# board_schematic.net
KiCad netlist of a schematic drawn in Altium Designer
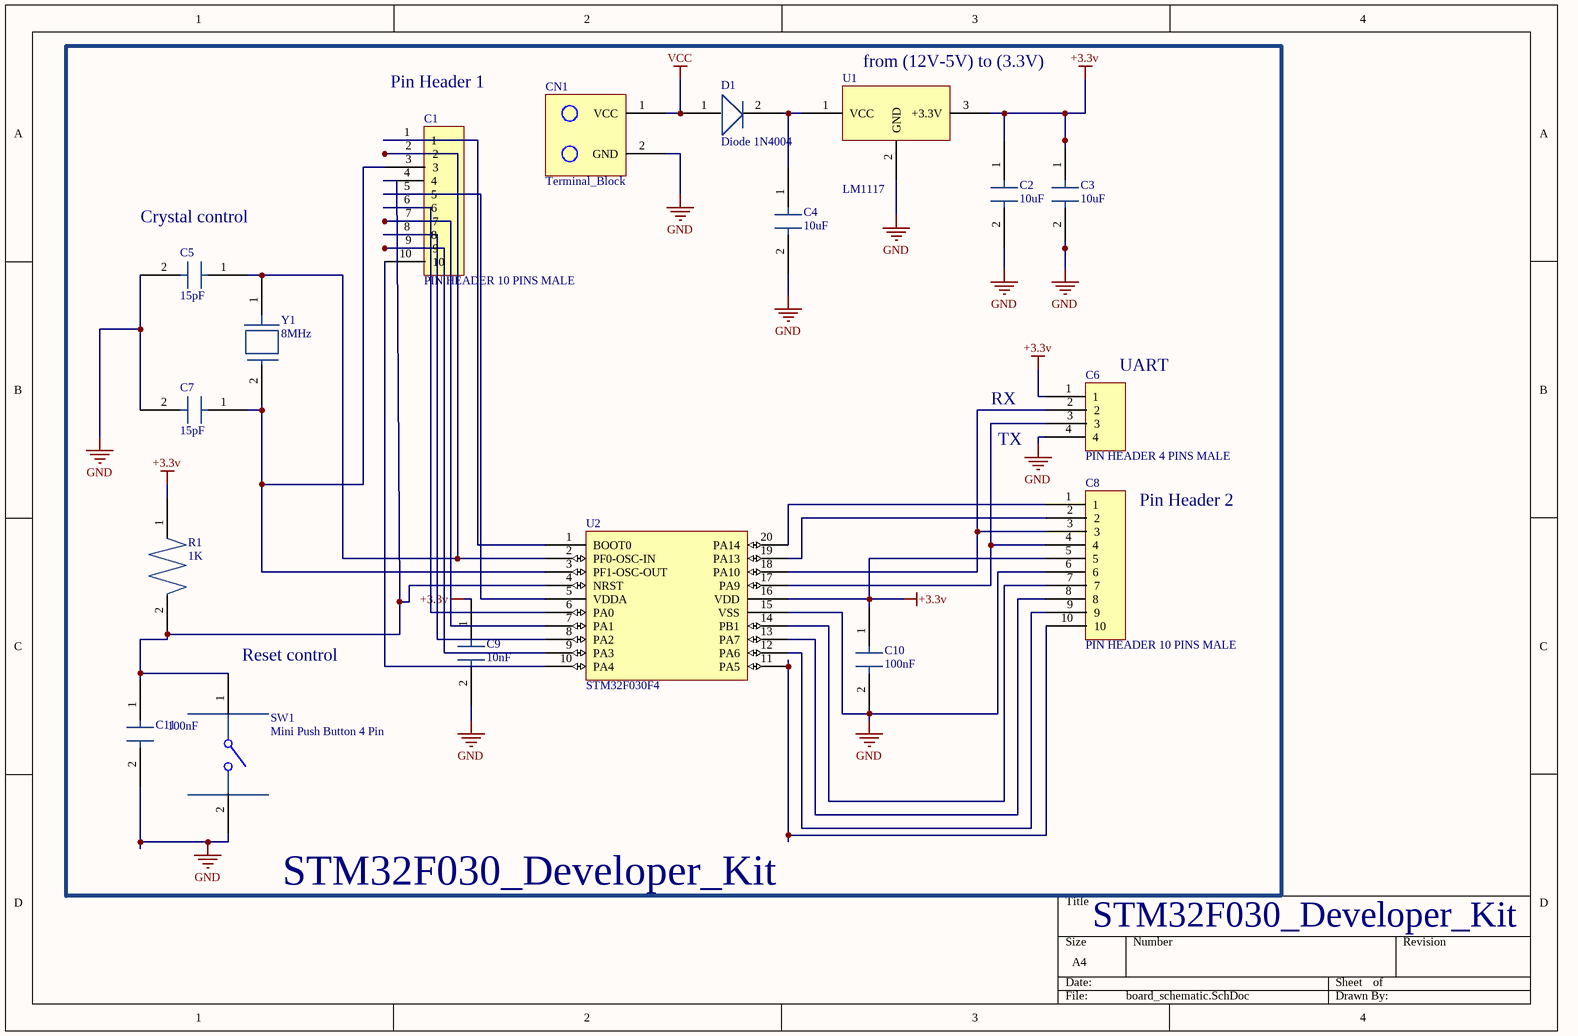
[diagram p0: board_schematic.SchDoc]

(export (version "E")
  (design (tool "Eeschema 10.0.6"))
  (components
    (comp (ref "C1")
      (value "PIN HEADER 10 PINS MALE")
      (footprint "PIN HEADER 10 PINS MALE")
      (description "Through Hole 1way 10pins")
      (fields (field (name "MANUFACTURER") "ZHOURI") (field (name "MANUFACTURER PART NUMBER") "2.54-1*10"))
      (libsource (lib "stm_library") (part "PIN HEADER 10 PINS MALE"))
    )
    (comp (ref "C2")
      (value "10uF")
      (footprint "CAP 220nF SMD")
      (description "25V 10uF Y5V ±10% 1206 Multilayer Ceramic Capacitors MLCC – SMD/SMT ROHS")
      (fields
        (field (name "MANUFACTURER") "CCTC")
        (field (name "MANUFACTURER PART NUMBER") "TCC1206X5R106K250HT")
      )
      (libsource (lib "stm_library") (part "CAP 10uF SMD"))
    )
    (comp (ref "C3")
      (value "10uF")
      (footprint "CAP 220nF SMD")
      (description "25V 10uF Y5V ±10% 1206 Multilayer Ceramic Capacitors MLCC – SMD/SMT ROHS")
      (fields
        (field (name "MANUFACTURER") "CCTC")
        (field (name "MANUFACTURER PART NUMBER") "TCC1206X5R106K250HT")
      )
      (libsource (lib "stm_library") (part "CAP 10uF SMD"))
    )
    (comp (ref "C4")
      (value "10uF")
      (footprint "CAP 220nF SMD")
      (description "25V 10uF Y5V ±10% 1206 Multilayer Ceramic Capacitors MLCC – SMD/SMT ROHS")
      (fields
        (field (name "MANUFACTURER") "CCTC")
        (field (name "MANUFACTURER PART NUMBER") "TCC1206X5R106K250HT")
      )
      (libsource (lib "stm_library") (part "CAP 10uF SMD"))
    )
    (comp (ref "C5")
      (value "15pF")
      (footprint "CAP 15pF SMD")
      (description "50V 15pF C0G ±5% 0603 Multilayer Ceramic Capacitors MLCC – SMD/SMT ROHS– SMD/SMT ROHS")
      (fields
        (field (name "MANUFACTURER") "CCTC")
        (field (name "MANUFACTURER PART NUMBER") "TCC0603COG150J500CT")
      )
      (libsource (lib "stm_library") (part "CAP 15pF SMD"))
    )
    (comp (ref "C6")
      (value "PIN HEADER 4 PINS MALE")
      (footprint "PIN HEADER 4 PINS MALE")
      (description "Through Hole 1way 4pins")
      (fields (field (name "MANUFACTURER") "ZHOURI") (field (name "MANUFACTURER PART NUMBER") "2.54-1*4"))
      (libsource (lib "stm_library") (part "PIN HEADER 4 PINS MALE"))
    )
    (comp (ref "C7")
      (value "15pF")
      (footprint "CAP 15pF SMD")
      (description "50V 15pF C0G ±5% 0603 Multilayer Ceramic Capacitors MLCC – SMD/SMT ROHS– SMD/SMT ROHS")
      (fields
        (field (name "MANUFACTURER") "CCTC")
        (field (name "MANUFACTURER PART NUMBER") "TCC0603COG150J500CT")
      )
      (libsource (lib "stm_library") (part "CAP 15pF SMD"))
    )
    (comp (ref "C8")
      (value "PIN HEADER 10 PINS MALE")
      (footprint "PIN HEADER 10 PINS MALE")
      (description "Through Hole 1way 10pins")
      (fields (field (name "MANUFACTURER") "ZHOURI") (field (name "MANUFACTURER PART NUMBER") "2.54-1*10"))
      (libsource (lib "stm_library") (part "PIN HEADER 10 PINS MALE"))
    )
    (comp (ref "C9")
      (value "10nF")
      (footprint "CAP 220nF SMD")
      (description "50V 10nF X7R ±10% 1206 Multilayer Ceramic Capacitors MLCC – SMD/SMT ROHS")
      (fields
        (field (name "MANUFACTURER") "CCTC")
        (field (name "MANUFACTURER PART NUMBER") "TCC1206X7R103K500DT")
      )
      (libsource (lib "stm_library") (part "CAP 10nF SMD"))
    )
    (comp (ref "C10")
      (value "100nF")
      (footprint "CAP 100nF SMD")
      (description "16V 100nF X7R ±10% 0402 Multilayer Ceramic Capacitors MLCC – SMD/SMT ROHS")
      (fields
        (field (name "MANUFACTURER") "Samsung Electro-Mechanics")
        (field (name "MANUFACTURER PART NUMBER") "CL05B104KO5NNNC")
      )
      (libsource (lib "stm_library") (part "CAP 100nF SMD"))
    )
    (comp (ref "C11")
      (value "100nF")
      (footprint "CAP 100nF SMD")
      (description "16V 100nF X7R ±10% 0402 Multilayer Ceramic Capacitors MLCC – SMD/SMT ROHS")
      (fields
        (field (name "MANUFACTURER") "Samsung Electro-Mechanics")
        (field (name "MANUFACTURER PART NUMBER") "CL05B104KO5NNNC")
      )
      (libsource (lib "stm_library") (part "CAP 100nF SMD"))
    )
    (comp (ref "CN1")
      (value "Terminal_Block")
      (footprint "TerminalBlock_2pins")
      (fields
        (field (name "MANUFACTURER") "CUI Devices")
        (field (name "MANUFACTURER PART NUMBER") "TB002-500-02BE")
      )
      (libsource (lib "stm_library") (part "Terminal_Block"))
    )
    (comp (ref "D1")
      (value "Diode 1N4004")
      (footprint "Diode 1N4004")
      (description "Single 1A 1.1V@1A 400V SMA Diodes – General Purpose ROHS")
      (fields (field (name "MANUFACTURER") "YONGYUTAI") (field (name "MANUFACTURER PART NUMBER") "1N4004"))
      (libsource (lib "stm_library") (part "Diode 1N4004"))
    )
    (comp (ref "R1")
      (value "1K")
      (footprint "RES 10K SMD")
      (description "Chip Resistor SMD 1KΩ ±5% 1W ±100ppm/℃ 2512")
      (fields
        (field (name "MANUFACTURER") "FOJAN")
        (field (name "MANUFACTURER PART NUMBER") "FRC2512J103 TS")
      )
      (libsource (lib "stm_library") (part "RES 1K SMD"))
    )
    (comp (ref "SW1")
      (value "Mini Push Button 4 Pin")
      (footprint "Mini Push Button 4 Pin")
      (description "6x6x7mm Tactile 4 Pin Push Button Switch")
      (fields
        (field (name "MANUFACTURER") "HYP (Hongyuan Precision)")
        (field (name "ANUFACTURER PART NUMBER") "1TS005F-2500-5001")
      )
      (libsource (lib "stm_library") (part "Mini Push Button 4 Pin"))
    )
    (comp (ref "U1")
      (value "LM1117")
      (footprint "LM1117")
      (description "3.3 SOT-233 Linear Voltage Regulators (LDO) 3.3V  Output Current 800mA")
      (fields (field (name "MANUFACTURER") "National semiconductors"))
      (libsource (lib "stm_library") (part "LM1117"))
    )
    (comp (ref "U2")
      (value "STM32F030F4")
      (footprint "STM32F030F4P6TR")
      (description ". TSSOP20 20-pin package pinout")
      (fields
        (field (name "MANUFACTURER") "STMicroelectronics")
        (field (name "MANUFACTURER PART NUMBER") "STM32F030F4P6TR")
      )
      (libsource (lib "stm_library") (part "STM32F030F4"))
    )
    (comp (ref "Y1")
      (value "8MHz")
      (footprint "Crystal 8MHz")
      (description "Crystal 8.000MHz 49S 20PPM 20pF 40Ω")
      (fields
        (field (name "MANUFACTURER") "HUIYUAN Crystal")
        (field (name "MANUFACTURER PART NUMBER") "HY8M49SOB2T02")
      )
      (libsource (lib "stm_library") (part "Crystal 8.000MHz"))
    )
  )
  (nets
    (net (code "1") (name "+3.3v") (class "Default")
      (node (ref "C10") (pin "1") (pinfunction "1_1") (pintype "passive"))
      (node (ref "C2") (pin "1") (pinfunction "1_1") (pintype "passive"))
      (node (ref "C3") (pin "1") (pinfunction "1_1") (pintype "passive"))
      (node (ref "C6") (pin "1") (pinfunction "1_1") (pintype "passive"))
      (node (ref "C8") (pin "5") (pinfunction "5_5") (pintype "passive"))
      (node (ref "C9") (pin "1") (pinfunction "1_1") (pintype "passive"))
      (node (ref "R1") (pin "1") (pinfunction "1_1") (pintype "passive"))
      (node (ref "U1") (pin "3") (pinfunction "+3.3V_3") (pintype "passive"))
      (node (ref "U2") (pin "16") (pinfunction "VDD_16") (pintype "passive"))
    )
    (net (code "2") (name "GND") (class "Default")
      (node (ref "C10") (pin "2") (pinfunction "2_2") (pintype "passive"))
      (node (ref "C11") (pin "2") (pinfunction "2_2") (pintype "passive"))
      (node (ref "C2") (pin "2") (pinfunction "2_2") (pintype "passive"))
      (node (ref "C3") (pin "2") (pinfunction "2_2") (pintype "passive"))
      (node (ref "C4") (pin "2") (pinfunction "2_2") (pintype "passive"))
      (node (ref "C5") (pin "2") (pinfunction "2_2") (pintype "passive"))
      (node (ref "C6") (pin "4") (pinfunction "4_4") (pintype "passive"))
      (node (ref "C7") (pin "2") (pinfunction "2_2") (pintype "passive"))
      (node (ref "C8") (pin "6") (pinfunction "6_6") (pintype "passive"))
      (node (ref "C9") (pin "2") (pinfunction "2_2") (pintype "passive"))
      (node (ref "CN1") (pin "2") (pinfunction "GND_2") (pintype "passive"))
      (node (ref "SW1") (pin "2") (pinfunction "2_2") (pintype "passive"))
      (node (ref "U1") (pin "2") (pinfunction "GND_2") (pintype "passive"))
      (node (ref "U2") (pin "15") (pinfunction "VSS_15") (pintype "passive"))
    )
    (net (code "3") (name "Net-(U1-VCC)") (class "Default")
      (node (ref "C4") (pin "1") (pinfunction "1_1") (pintype "passive"))
      (node (ref "D1") (pin "2") (pinfunction "2_2") (pintype "passive"))
      (node (ref "U1") (pin "1") (pinfunction "VCC_1") (pintype "passive"))
    )
    (net (code "4") (name "Net-(U2-BOOT0)") (class "Default")
      (node (ref "C1") (pin "1") (pinfunction "1_1") (pintype "passive"))
      (node (ref "U2") (pin "1") (pinfunction "BOOT0_1") (pintype "passive"))
    )
    (net (code "5") (name "Net-(U2-NRST)") (class "Default")
      (node (ref "C1") (pin "4") (pinfunction "4_4") (pintype "passive"))
      (node (ref "C11") (pin "1") (pinfunction "1_1") (pintype "passive"))
      (node (ref "R1") (pin "2") (pinfunction "2_2") (pintype "passive"))
      (node (ref "SW1") (pin "1") (pinfunction "1_1") (pintype "passive"))
      (node (ref "U2") (pin "4") (pinfunction "NRST_4") (pintype "bidirectional"))
    )
    (net (code "6") (name "Net-(U2-PA0)") (class "Default")
      (node (ref "C1") (pin "6") (pinfunction "6_6") (pintype "passive"))
      (node (ref "U2") (pin "6") (pinfunction "PA0_6") (pintype "bidirectional"))
    )
    (net (code "7") (name "Net-(U2-PA1)") (class "Default")
      (node (ref "C1") (pin "7") (pinfunction "7_7") (pintype "passive"))
      (node (ref "U2") (pin "7") (pinfunction "PA1_7") (pintype "bidirectional"))
    )
    (net (code "8") (name "Net-(U2-PA2)") (class "Default")
      (node (ref "C1") (pin "8") (pinfunction "8_8") (pintype "passive"))
      (node (ref "U2") (pin "8") (pinfunction "PA2_8") (pintype "bidirectional"))
    )
    (net (code "9") (name "Net-(U2-PA3)") (class "Default")
      (node (ref "C1") (pin "9") (pinfunction "9_9") (pintype "passive"))
      (node (ref "U2") (pin "9") (pinfunction "PA3_9") (pintype "bidirectional"))
    )
    (net (code "10") (name "Net-(U2-PA4)") (class "Default")
      (node (ref "C1") (pin "10") (pinfunction "10_10") (pintype "passive"))
      (node (ref "U2") (pin "10") (pinfunction "PA4_10") (pintype "bidirectional"))
    )
    (net (code "11") (name "Net-(U2-PA5)") (class "Default")
      (node (ref "C8") (pin "10") (pinfunction "10_10") (pintype "passive"))
      (node (ref "U2") (pin "11") (pinfunction "PA5_11") (pintype "bidirectional"))
    )
    (net (code "12") (name "Net-(U2-PA6)") (class "Default")
      (node (ref "C8") (pin "9") (pinfunction "9_9") (pintype "passive"))
      (node (ref "U2") (pin "12") (pinfunction "PA6_12") (pintype "bidirectional"))
    )
    (net (code "13") (name "Net-(U2-PA7)") (class "Default")
      (node (ref "C8") (pin "8") (pinfunction "8_8") (pintype "passive"))
      (node (ref "U2") (pin "13") (pinfunction "PA7_13") (pintype "bidirectional"))
    )
    (net (code "14") (name "Net-(U2-PA9)") (class "Default")
      (node (ref "C6") (pin "3") (pinfunction "3_3") (pintype "passive"))
      (node (ref "C8") (pin "4") (pinfunction "4_4") (pintype "passive"))
      (node (ref "U2") (pin "17") (pinfunction "PA9_17") (pintype "bidirectional"))
    )
    (net (code "15") (name "Net-(U2-PA10)") (class "Default")
      (node (ref "C6") (pin "2") (pinfunction "2_2") (pintype "passive"))
      (node (ref "C8") (pin "3") (pinfunction "3_3") (pintype "passive"))
      (node (ref "U2") (pin "18") (pinfunction "PA10_18") (pintype "bidirectional"))
    )
    (net (code "16") (name "Net-(U2-PA13)") (class "Default")
      (node (ref "C8") (pin "2") (pinfunction "2_2") (pintype "passive"))
      (node (ref "U2") (pin "19") (pinfunction "PA13_19") (pintype "bidirectional"))
    )
    (net (code "17") (name "Net-(U2-PA14)") (class "Default")
      (node (ref "C8") (pin "1") (pinfunction "1_1") (pintype "passive"))
      (node (ref "U2") (pin "20") (pinfunction "PA14_20") (pintype "bidirectional"))
    )
    (net (code "18") (name "Net-(U2-PB1)") (class "Default")
      (node (ref "C8") (pin "7") (pinfunction "7_7") (pintype "passive"))
      (node (ref "U2") (pin "14") (pinfunction "PB1_14") (pintype "bidirectional"))
    )
    (net (code "19") (name "Net-(U2-PF0-OSC-IN)") (class "Default")
      (node (ref "C1") (pin "2") (pinfunction "2_2") (pintype "passive"))
      (node (ref "C5") (pin "1") (pinfunction "1_1") (pintype "passive"))
      (node (ref "U2") (pin "2") (pinfunction "PF0-OSC-IN_2") (pintype "bidirectional"))
      (node (ref "Y1") (pin "1") (pinfunction "1_1") (pintype "passive"))
    )
    (net (code "20") (name "Net-(U2-PF1-OSC-OUT)") (class "Default")
      (node (ref "C1") (pin "3") (pinfunction "3_3") (pintype "passive"))
      (node (ref "C7") (pin "1") (pinfunction "1_1") (pintype "passive"))
      (node (ref "U2") (pin "3") (pinfunction "PF1-OSC-OUT_3") (pintype "bidirectional"))
      (node (ref "Y1") (pin "2") (pinfunction "2_2") (pintype "passive"))
    )
    (net (code "21") (name "Net-(U2-VDDA)") (class "Default")
      (node (ref "C1") (pin "5") (pinfunction "5_5") (pintype "passive"))
      (node (ref "U2") (pin "5") (pinfunction "VDDA_5") (pintype "passive"))
    )
    (net (code "22") (name "VCC") (class "Default")
      (node (ref "CN1") (pin "1") (pinfunction "VCC_1") (pintype "passive"))
      (node (ref "D1") (pin "1") (pinfunction "1_1") (pintype "passive"))
    )
  )
)
